# Schematic.net
KiCad netlist of a schematic drawn in EAGLE
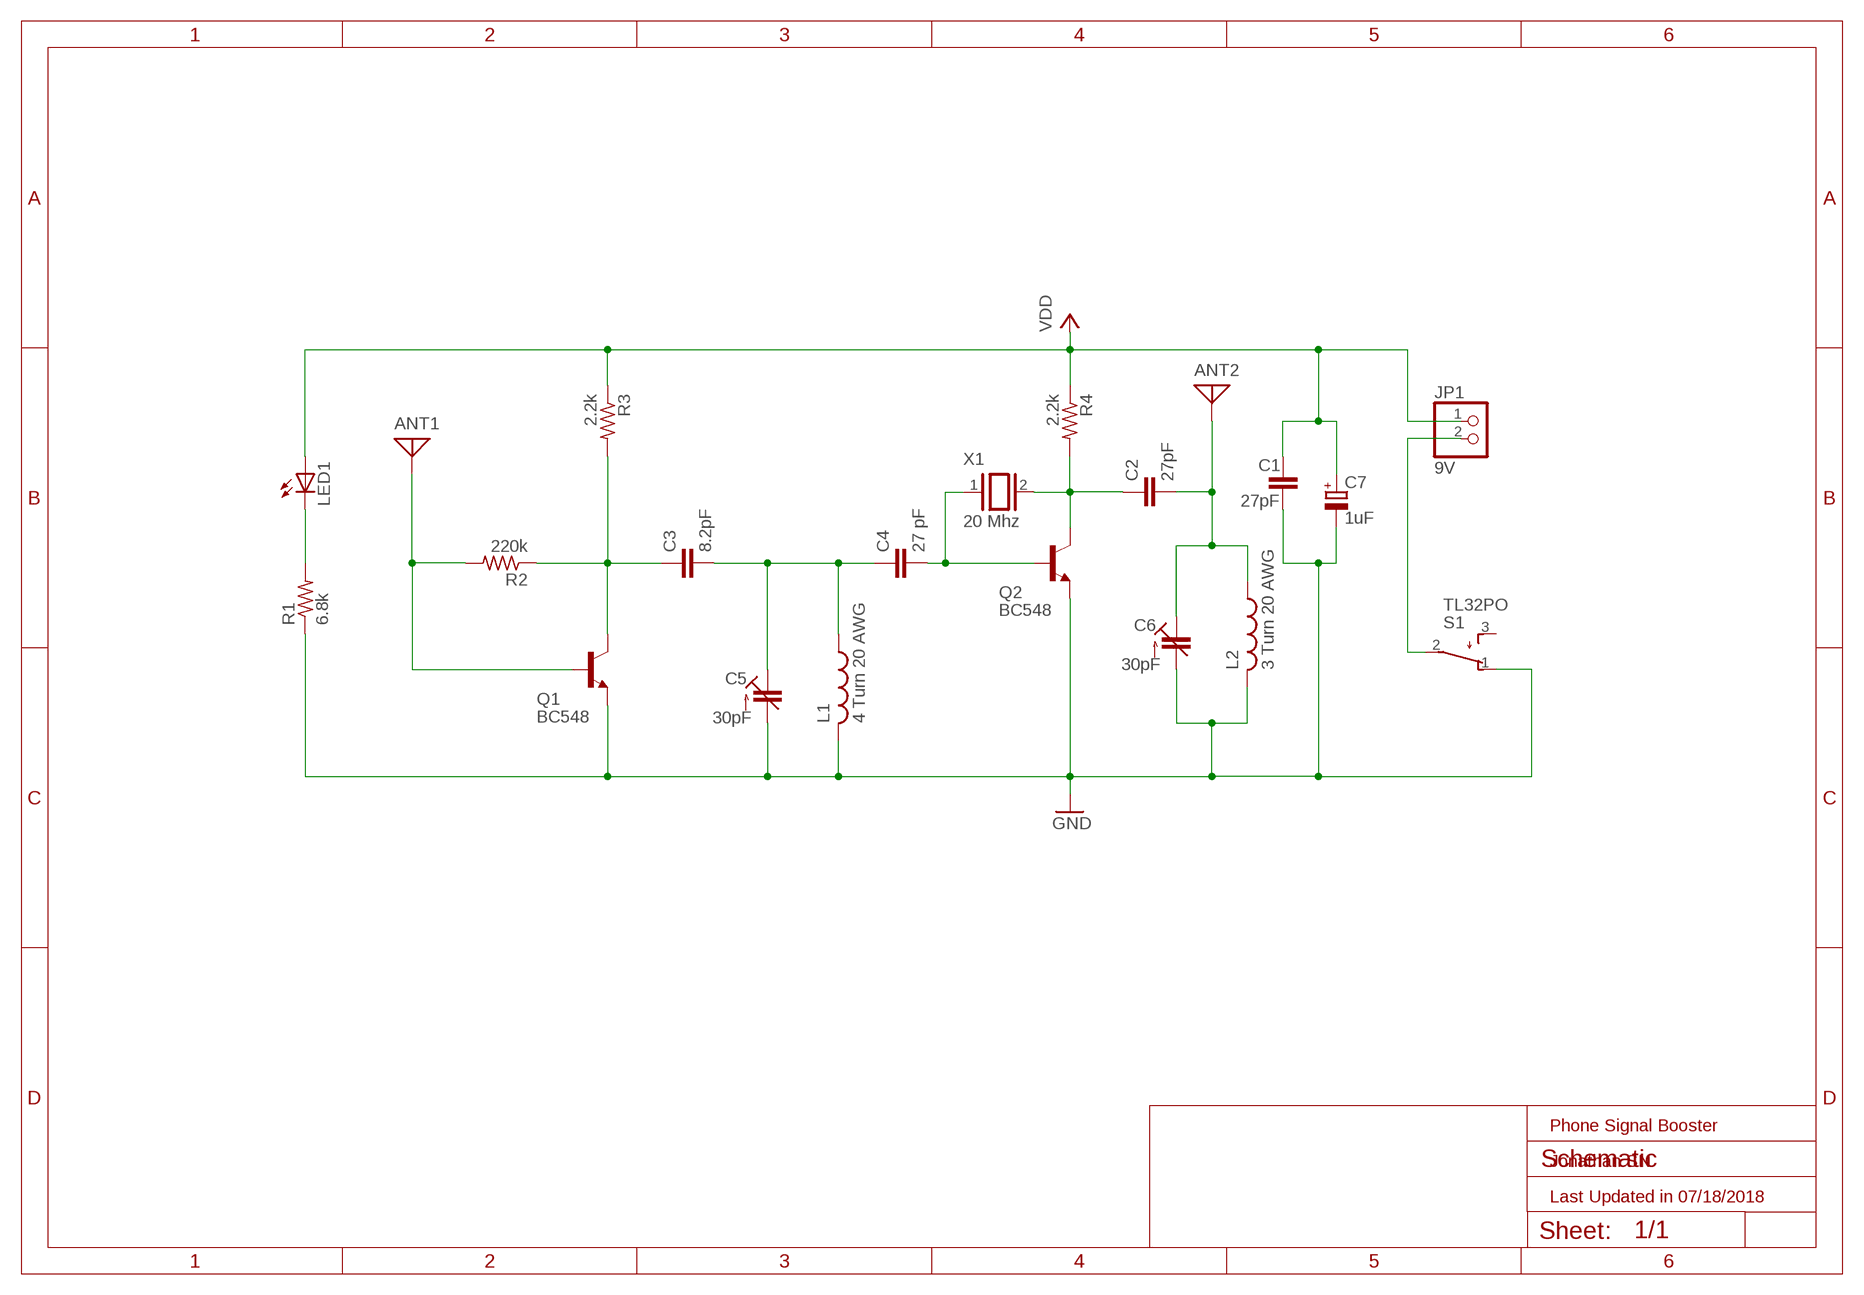
[diagram p0: schematic, sheet 1]

(export (version "E")
  (design (tool "Eeschema 10.0.6"))
  (components
    (comp (ref "ANT1")
      (value "ANTENNA")
      (footprint "eagle-import:PAD-01")
      (libsource (lib "eagle-import") (part "ANTENNA"))
    )
    (comp (ref "ANT2")
      (value "ANTENNA")
      (footprint "eagle-import:PAD-01")
      (libsource (lib "eagle-import") (part "ANTENNA"))
    )
    (comp (ref "C1")
      (value "27pF")
      (footprint "eagle-import:C2.5-3")
      (libsource (lib "eagle-import") (part "C2,5-3"))
    )
    (comp (ref "C2")
      (value "27pF")
      (footprint "eagle-import:C2.5-3")
      (libsource (lib "eagle-import") (part "C2,5-3"))
    )
    (comp (ref "C3")
      (value "8.2pF")
      (footprint "eagle-import:C2.5-3")
      (libsource (lib "eagle-import") (part "C2,5-3"))
    )
    (comp (ref "C4")
      (value "27 pF")
      (footprint "eagle-import:C2.5-3")
      (libsource (lib "eagle-import") (part "C2,5-3"))
    )
    (comp (ref "C5")
      (value "30pF")
      (footprint "eagle-import:CTRIM808-BC")
      (libsource (lib "eagle-import") (part "C-TRIMM808"))
    )
    (comp (ref "C6")
      (value "30pF")
      (footprint "eagle-import:CTRIM808-BC")
      (libsource (lib "eagle-import") (part "C-TRIMM808"))
    )
    (comp (ref "C7")
      (value "1uF")
      (footprint "eagle-import:E2-5")
      (libsource (lib "eagle-import") (part "CPOL-EUE2-5"))
    )
    (comp (ref "JP1")
      (value "9V")
      (footprint "eagle-import:1X02")
      (libsource (lib "eagle-import") (part "PINHD-1X2"))
    )
    (comp (ref "L1")
      (value "4 Turn 20 AWG")
      (footprint "eagle-import:0204_5")
      (libsource (lib "eagle-import") (part "L-US0204/5"))
    )
    (comp (ref "L2")
      (value "3 Turn 20 AWG")
      (footprint "eagle-import:0204_5")
      (libsource (lib "eagle-import") (part "L-US0204/5"))
    )
    (comp (ref "LED1")
      (value "LED3MM")
      (footprint "eagle-import:LED3MM")
      (libsource (lib "eagle-import") (part "LED3MM"))
    )
    (comp (ref "Q1")
      (value "BC548")
      (footprint "eagle-import:TO92-EBC")
      (libsource (lib "eagle-import") (part "BC548"))
    )
    (comp (ref "Q2")
      (value "BC548")
      (footprint "eagle-import:TO92-EBC")
      (libsource (lib "eagle-import") (part "BC548"))
    )
    (comp (ref "R1")
      (value "6.8k")
      (footprint "eagle-import:0207_7")
      (libsource (lib "eagle-import") (part "R-US_0207/7"))
    )
    (comp (ref "R2")
      (value "220k")
      (footprint "eagle-import:0207_7")
      (libsource (lib "eagle-import") (part "R-US_0207/7"))
    )
    (comp (ref "R3")
      (value "2.2k")
      (footprint "eagle-import:0207_7")
      (libsource (lib "eagle-import") (part "R-US_0207/7"))
    )
    (comp (ref "R4")
      (value "2.2k")
      (footprint "eagle-import:0207_7")
      (libsource (lib "eagle-import") (part "R-US_0207/7"))
    )
    (comp (ref "S1")
      (value "TL32PO")
      (footprint "eagle-import:TL3XPO")
      (libsource (lib "eagle-import") (part "TL32PO"))
    )
    (comp (ref "X1")
      (value "20 Mhz")
      (footprint "eagle-import:QS")
      (libsource (lib "eagle-import") (part "XTAL/S"))
    )
  )
  (nets
    (net (code "1") (name "GND") (class "Default")
      (node (ref "C1") (pin "2") (pinfunction "2_2") (pintype "passive"))
      (node (ref "C5") (pin "2") (pinfunction "A_2") (pintype "passive"))
      (node (ref "C6") (pin "2") (pinfunction "A_2") (pintype "passive"))
      (node (ref "C7") (pin "-") (pinfunction "-_-") (pintype "passive"))
      (node (ref "L1") (pin "2") (pinfunction "2_2") (pintype "passive"))
      (node (ref "L2") (pin "2") (pinfunction "2_2") (pintype "passive"))
      (node (ref "Q1") (pin "E") (pinfunction "E_E") (pintype "passive"))
      (node (ref "Q2") (pin "E") (pinfunction "E_E") (pintype "passive"))
      (node (ref "R1") (pin "1") (pinfunction "1_1") (pintype "passive"))
      (node (ref "S1") (pin "1") (pinfunction "O_1") (pintype "passive"))
    )
    (net (code "2") (name "Net-(ANT1-Pad1)") (class "Default")
      (node (ref "ANT1") (pin "1") (pinfunction "1_1") (pintype "output"))
      (node (ref "Q1") (pin "B") (pinfunction "B_B") (pintype "passive"))
      (node (ref "R2") (pin "2") (pinfunction "2_2") (pintype "passive"))
    )
    (net (code "3") (name "Net-(C2-Pad1)") (class "Default")
      (node (ref "C2") (pin "1") (pinfunction "1_1") (pintype "passive"))
      (node (ref "Q2") (pin "C") (pinfunction "C_C") (pintype "passive"))
      (node (ref "R4") (pin "2") (pinfunction "2_2") (pintype "passive"))
      (node (ref "X1") (pin "2") (pinfunction "2_2") (pintype "passive"))
    )
    (net (code "4") (name "Net-(C3-Pad1)") (class "Default")
      (node (ref "C3") (pin "1") (pinfunction "1_1") (pintype "passive"))
      (node (ref "Q1") (pin "C") (pinfunction "C_C") (pintype "passive"))
      (node (ref "R2") (pin "1") (pinfunction "1_1") (pintype "passive"))
      (node (ref "R3") (pin "2") (pinfunction "2_2") (pintype "passive"))
    )
    (net (code "5") (name "Net-(C4-Pad2)") (class "Default")
      (node (ref "C4") (pin "2") (pinfunction "2_2") (pintype "passive"))
      (node (ref "Q2") (pin "B") (pinfunction "B_B") (pintype "passive"))
      (node (ref "X1") (pin "1") (pinfunction "1_1") (pintype "passive"))
    )
    (net (code "6") (name "Net-(C5-E)") (class "Default")
      (node (ref "C3") (pin "2") (pinfunction "2_2") (pintype "passive"))
      (node (ref "C4") (pin "1") (pinfunction "1_1") (pintype "passive"))
      (node (ref "C5") (pin "1") (pinfunction "E_1") (pintype "passive"))
      (node (ref "L1") (pin "1") (pinfunction "1_1") (pintype "passive"))
    )
    (net (code "7") (name "Net-(C6-E)") (class "Default")
      (node (ref "ANT2") (pin "1") (pinfunction "1_1") (pintype "output"))
      (node (ref "C2") (pin "2") (pinfunction "2_2") (pintype "passive"))
      (node (ref "C6") (pin "1") (pinfunction "E_1") (pintype "passive"))
      (node (ref "L2") (pin "1") (pinfunction "1_1") (pintype "passive"))
    )
    (net (code "8") (name "Net-(LED1-C)") (class "Default")
      (node (ref "LED1") (pin "K") (pinfunction "C_K") (pintype "passive"))
      (node (ref "R1") (pin "2") (pinfunction "2_2") (pintype "passive"))
    )
    (net (code "9") (name "Net-(S1-P)") (class "Default")
      (node (ref "JP1") (pin "2") (pinfunction "2_2") (pintype "passive"))
      (node (ref "S1") (pin "2") (pinfunction "P_2") (pintype "passive"))
    )
    (net (code "10") (name "VDD") (class "Default")
      (node (ref "C1") (pin "1") (pinfunction "1_1") (pintype "passive"))
      (node (ref "C7") (pin "+") (pinfunction "+_+") (pintype "passive"))
      (node (ref "JP1") (pin "1") (pinfunction "1_1") (pintype "passive"))
      (node (ref "LED1") (pin "A") (pinfunction "A_A") (pintype "passive"))
      (node (ref "R3") (pin "1") (pinfunction "1_1") (pintype "passive"))
      (node (ref "R4") (pin "1") (pinfunction "1_1") (pintype "passive"))
    )
    (net (code "11") (name "unconnected-(S1-S-Pad3)") (class "Default")
      (node (ref "S1") (pin "3") (pinfunction "S_3") (pintype "passive"))
    )
  )
)
